# ME433_1.net
KiCad netlist of a schematic drawn in EAGLE
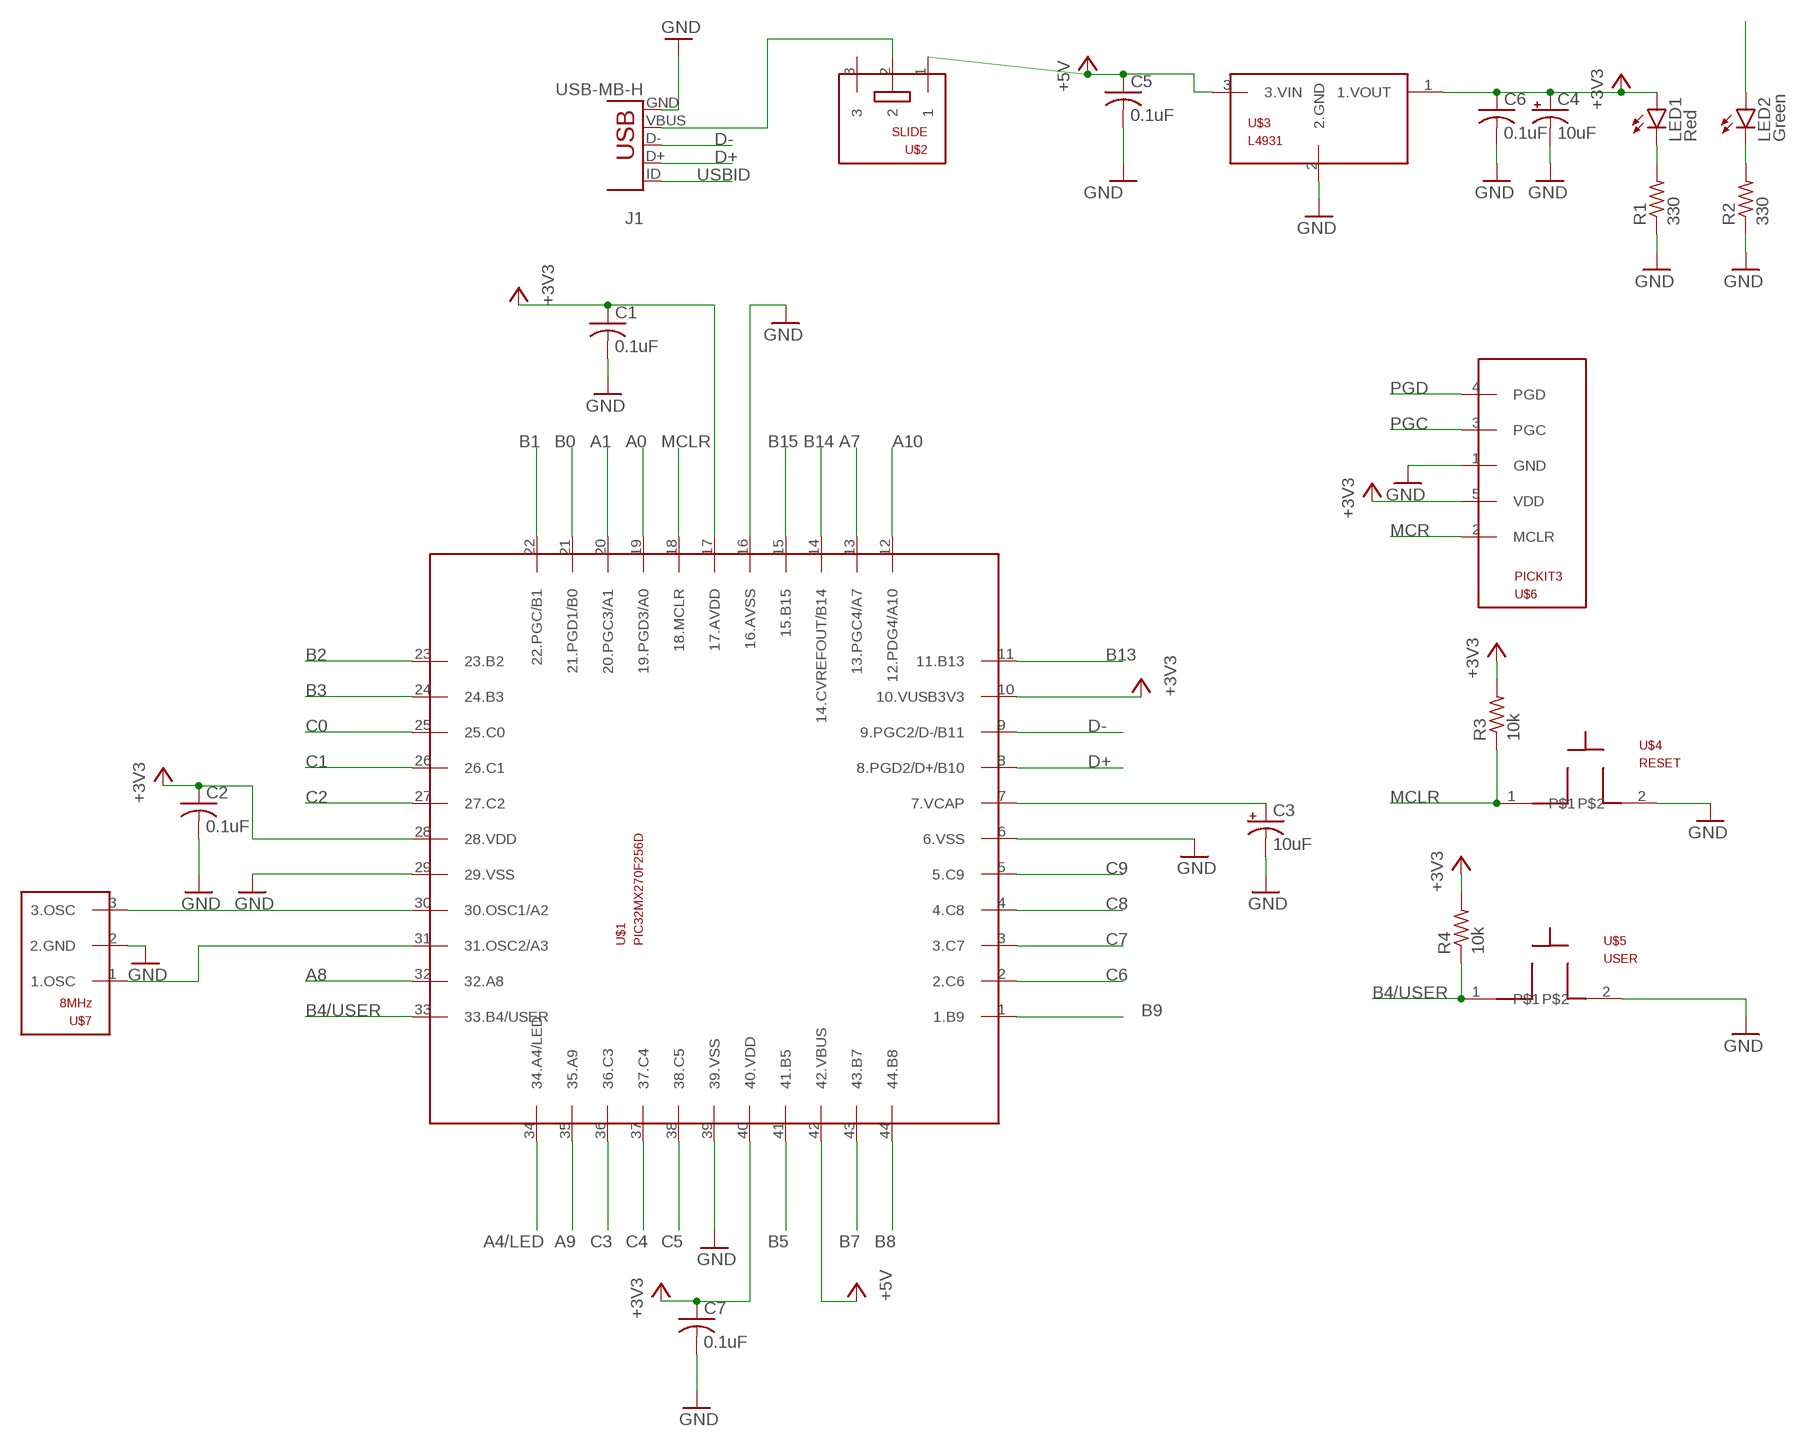
[diagram p0: schematic, sheet 1]

(export (version "E")
  (design (tool "Eeschema 10.0.6"))
  (components
    (comp (ref "C1")
      (value "0.1uF")
      (footprint "eagle-import:C025-025X050")
      (libsource (lib "eagle-import") (part "C-US025-025X050"))
    )
    (comp (ref "C2")
      (value "0.1uF")
      (footprint "eagle-import:C025-025X050")
      (libsource (lib "eagle-import") (part "C-US025-025X050"))
    )
    (comp (ref "C3")
      (value "10uF")
      (footprint "eagle-import:B45181B")
      (libsource (lib "eagle-import") (part "CPOL-USB45181B"))
    )
    (comp (ref "C4")
      (value "10uF")
      (footprint "eagle-import:B45181B")
      (libsource (lib "eagle-import") (part "CPOL-USB45181B"))
    )
    (comp (ref "C5")
      (value "0.1uF")
      (footprint "eagle-import:C025-025X050")
      (libsource (lib "eagle-import") (part "C-US025-025X050"))
    )
    (comp (ref "C6")
      (value "0.1uF")
      (footprint "eagle-import:C025-025X050")
      (libsource (lib "eagle-import") (part "C-US025-025X050"))
    )
    (comp (ref "C7")
      (value "0.1uF")
      (footprint "eagle-import:C025-025X050")
      (libsource (lib "eagle-import") (part "C-US025-025X050"))
    )
    (comp (ref "J1")
      (value "USB-MB-H")
      (footprint "eagle-import:USB-MB-H")
      (libsource (lib "eagle-import") (part "USB-MB-H"))
    )
    (comp (ref "LED1")
      (value "Red")
      (footprint "eagle-import:LED3MM")
      (libsource (lib "eagle-import") (part "LED3MM"))
    )
    (comp (ref "LED2")
      (value "Green")
      (footprint "eagle-import:LED3MM")
      (libsource (lib "eagle-import") (part "LED3MM"))
    )
    (comp (ref "R1")
      (value "330")
      (footprint "eagle-import:0207_10")
      (libsource (lib "eagle-import") (part "R-US_0207/10"))
    )
    (comp (ref "R2")
      (value "330")
      (footprint "eagle-import:0207_10")
      (libsource (lib "eagle-import") (part "R-US_0207/10"))
    )
    (comp (ref "R3")
      (value "10k")
      (footprint "eagle-import:0207_10")
      (libsource (lib "eagle-import") (part "R-US_0207/10"))
    )
    (comp (ref "R4")
      (value "10k")
      (footprint "eagle-import:0207_10")
      (libsource (lib "eagle-import") (part "R-US_0207/10"))
    )
    (comp (ref "U$1")
      (value "PIC32MX270F256D")
      (footprint "eagle-import:TQFP44")
      (libsource (lib "eagle-import") (part "PIC32MX270F256D"))
    )
    (comp (ref "U$2")
      (value "SLIDE")
      (footprint "eagle-import:SLIDE")
      (libsource (lib "eagle-import") (part "SLIDE"))
    )
    (comp (ref "U$3")
      (value "L4931")
      (footprint "eagle-import:1X03VREG")
      (libsource (lib "eagle-import") (part "L4931"))
    )
    (comp (ref "U$4")
      (value "RESET")
      (footprint "eagle-import:PB")
      (libsource (lib "eagle-import") (part "PB"))
    )
    (comp (ref "U$5")
      (value "USER")
      (footprint "eagle-import:PB")
      (libsource (lib "eagle-import") (part "PB"))
    )
    (comp (ref "U$6")
      (value "PICKIT3")
      (footprint "eagle-import:1X05")
      (libsource (lib "eagle-import") (part "PICKIT3"))
    )
    (comp (ref "U$7")
      (value "8MHz")
      (footprint "eagle-import:OSC")
      (libsource (lib "eagle-import") (part "OSC"))
    )
  )
  (nets
    (net (code "1") (name "+3V3") (class "Default")
      (node (ref "C1") (pin "1") (pinfunction "1_1") (pintype "passive"))
      (node (ref "C2") (pin "1") (pinfunction "1_1") (pintype "passive"))
      (node (ref "C4") (pin "+") (pinfunction "+_+") (pintype "passive"))
      (node (ref "C6") (pin "1") (pinfunction "1_1") (pintype "passive"))
      (node (ref "C7") (pin "1") (pinfunction "1_1") (pintype "passive"))
      (node (ref "LED1") (pin "A") (pinfunction "A_A") (pintype "passive"))
      (node (ref "R3") (pin "2") (pinfunction "2_2") (pintype "passive"))
      (node (ref "R4") (pin "2") (pinfunction "2_2") (pintype "passive"))
      (node (ref "U$1") (pin "10") (pinfunction "10.VUSB3V3_10") (pintype "bidirectional"))
      (node (ref "U$1") (pin "17") (pinfunction "17.AVDD_17") (pintype "bidirectional"))
      (node (ref "U$1") (pin "28") (pinfunction "28.VDD_28") (pintype "bidirectional"))
      (node (ref "U$1") (pin "40") (pinfunction "40.VDD_40") (pintype "bidirectional"))
      (node (ref "U$3") (pin "1") (pinfunction "1.VOUT_1") (pintype "bidirectional"))
      (node (ref "U$6") (pin "5") (pinfunction "VDD_5") (pintype "bidirectional"))
    )
    (net (code "2") (name "+5V") (class "Default")
      (node (ref "C5") (pin "1") (pinfunction "1_1") (pintype "passive"))
      (node (ref "U$1") (pin "42") (pinfunction "42.VBUS_42") (pintype "bidirectional"))
      (node (ref "U$2") (pin "1") (pinfunction "1_1") (pintype "bidirectional"))
      (node (ref "U$3") (pin "3") (pinfunction "3.VIN_3") (pintype "bidirectional"))
    )
    (net (code "3") (name "/A0") (class "Default")
      (node (ref "U$1") (pin "19") (pinfunction "19.PGD3/A0_19") (pintype "bidirectional"))
    )
    (net (code "4") (name "/A1") (class "Default")
      (node (ref "U$1") (pin "20") (pinfunction "20.PGC3/A1_20") (pintype "bidirectional"))
    )
    (net (code "5") (name "/A4{slash}LED") (class "Default")
      (node (ref "LED2") (pin "A") (pinfunction "A_A") (pintype "passive"))
      (node (ref "U$1") (pin "34") (pinfunction "34.A4/LED_34") (pintype "bidirectional"))
    )
    (net (code "6") (name "/A7") (class "Default")
      (node (ref "U$1") (pin "13") (pinfunction "13.PGC4/A7_13") (pintype "bidirectional"))
    )
    (net (code "7") (name "/A8") (class "Default")
      (node (ref "U$1") (pin "32") (pinfunction "32.A8_32") (pintype "bidirectional"))
    )
    (net (code "8") (name "/A9") (class "Default")
      (node (ref "U$1") (pin "35") (pinfunction "35.A9_35") (pintype "bidirectional"))
    )
    (net (code "9") (name "/A10") (class "Default")
      (node (ref "U$1") (pin "12") (pinfunction "12.PDG4/A10_12") (pintype "bidirectional"))
    )
    (net (code "10") (name "/B0") (class "Default")
      (node (ref "U$1") (pin "21") (pinfunction "21.PGD1/B0_21") (pintype "bidirectional"))
    )
    (net (code "11") (name "/B1") (class "Default")
      (node (ref "U$1") (pin "22") (pinfunction "22.PGC/B1_22") (pintype "bidirectional"))
    )
    (net (code "12") (name "/B2") (class "Default")
      (node (ref "U$1") (pin "23") (pinfunction "23.B2_23") (pintype "bidirectional"))
    )
    (net (code "13") (name "/B3") (class "Default")
      (node (ref "U$1") (pin "24") (pinfunction "24.B3_24") (pintype "bidirectional"))
    )
    (net (code "14") (name "/B4{slash}USER") (class "Default")
      (node (ref "R4") (pin "1") (pinfunction "1_1") (pintype "passive"))
      (node (ref "U$1") (pin "33") (pinfunction "33.B4/USER_33") (pintype "bidirectional"))
      (node (ref "U$5") (pin "1") (pinfunction "P$1_1") (pintype "bidirectional"))
    )
    (net (code "15") (name "/B5") (class "Default")
      (node (ref "U$1") (pin "41") (pinfunction "41.B5_41") (pintype "bidirectional"))
    )
    (net (code "16") (name "/B7") (class "Default")
      (node (ref "U$1") (pin "43") (pinfunction "43.B7_43") (pintype "bidirectional"))
    )
    (net (code "17") (name "/B8") (class "Default")
      (node (ref "U$1") (pin "44") (pinfunction "44.B8_44") (pintype "bidirectional"))
    )
    (net (code "18") (name "/B9") (class "Default")
      (node (ref "U$1") (pin "1") (pinfunction "1.B9_1") (pintype "bidirectional"))
    )
    (net (code "19") (name "/B13") (class "Default")
      (node (ref "U$1") (pin "11") (pinfunction "11.B13_11") (pintype "bidirectional"))
    )
    (net (code "20") (name "/B14") (class "Default")
      (node (ref "U$1") (pin "14") (pinfunction "14.CVREFOUT/B14_14") (pintype "bidirectional"))
    )
    (net (code "21") (name "/B15") (class "Default")
      (node (ref "U$1") (pin "15") (pinfunction "15.B15_15") (pintype "bidirectional"))
    )
    (net (code "22") (name "/C0") (class "Default")
      (node (ref "U$1") (pin "25") (pinfunction "25.C0_25") (pintype "bidirectional"))
    )
    (net (code "23") (name "/C1") (class "Default")
      (node (ref "U$1") (pin "26") (pinfunction "26.C1_26") (pintype "bidirectional"))
    )
    (net (code "24") (name "/C2") (class "Default")
      (node (ref "U$1") (pin "27") (pinfunction "27.C2_27") (pintype "bidirectional"))
    )
    (net (code "25") (name "/C3") (class "Default")
      (node (ref "U$1") (pin "36") (pinfunction "36.C3_36") (pintype "bidirectional"))
    )
    (net (code "26") (name "/C4") (class "Default")
      (node (ref "U$1") (pin "37") (pinfunction "37.C4_37") (pintype "bidirectional"))
    )
    (net (code "27") (name "/C5") (class "Default")
      (node (ref "U$1") (pin "38") (pinfunction "38.C5_38") (pintype "bidirectional"))
    )
    (net (code "28") (name "/C6") (class "Default")
      (node (ref "U$1") (pin "2") (pinfunction "2.C6_2") (pintype "bidirectional"))
    )
    (net (code "29") (name "/C7") (class "Default")
      (node (ref "U$1") (pin "3") (pinfunction "3.C7_3") (pintype "bidirectional"))
    )
    (net (code "30") (name "/C8") (class "Default")
      (node (ref "U$1") (pin "4") (pinfunction "4.C8_4") (pintype "bidirectional"))
    )
    (net (code "31") (name "/C9") (class "Default")
      (node (ref "U$1") (pin "5") (pinfunction "5.C9_5") (pintype "bidirectional"))
    )
    (net (code "32") (name "/D+") (class "Default")
      (node (ref "J1") (pin "D+") (pinfunction "D+_D+") (pintype "bidirectional"))
      (node (ref "U$1") (pin "8") (pinfunction "8.PGD2/D+/B10_8") (pintype "bidirectional"))
    )
    (net (code "33") (name "/D-") (class "Default")
      (node (ref "J1") (pin "D-") (pinfunction "D-_D-") (pintype "bidirectional"))
      (node (ref "U$1") (pin "9") (pinfunction "9.PGC2/D-/B11_9") (pintype "bidirectional"))
    )
    (net (code "34") (name "/MCLR") (class "Default")
      (node (ref "R3") (pin "1") (pinfunction "1_1") (pintype "passive"))
      (node (ref "U$1") (pin "18") (pinfunction "18.MCLR_18") (pintype "bidirectional"))
      (node (ref "U$4") (pin "1") (pinfunction "P$1_1") (pintype "bidirectional"))
    )
    (net (code "35") (name "/MCR") (class "Default")
      (node (ref "U$6") (pin "2") (pinfunction "MCLR_2") (pintype "bidirectional"))
    )
    (net (code "36") (name "/PGC") (class "Default")
      (node (ref "U$6") (pin "3") (pinfunction "PGC_3") (pintype "bidirectional"))
    )
    (net (code "37") (name "/PGD") (class "Default")
      (node (ref "U$6") (pin "4") (pinfunction "PGD_4") (pintype "bidirectional"))
    )
    (net (code "38") (name "/USBID") (class "Default")
      (node (ref "J1") (pin "ID") (pinfunction "ID_ID") (pintype "bidirectional"))
    )
    (net (code "39") (name "GND") (class "Default")
      (node (ref "C1") (pin "2") (pinfunction "2_2") (pintype "passive"))
      (node (ref "C2") (pin "2") (pinfunction "2_2") (pintype "passive"))
      (node (ref "C3") (pin "-") (pinfunction "-_-") (pintype "passive"))
      (node (ref "C4") (pin "-") (pinfunction "-_-") (pintype "passive"))
      (node (ref "C5") (pin "2") (pinfunction "2_2") (pintype "passive"))
      (node (ref "C6") (pin "2") (pinfunction "2_2") (pintype "passive"))
      (node (ref "C7") (pin "2") (pinfunction "2_2") (pintype "passive"))
      (node (ref "J1") (pin "GND") (pinfunction "GND_GND") (pintype "bidirectional"))
      (node (ref "R1") (pin "1") (pinfunction "1_1") (pintype "passive"))
      (node (ref "R2") (pin "1") (pinfunction "1_1") (pintype "passive"))
      (node (ref "U$1") (pin "16") (pinfunction "16.AVSS_16") (pintype "bidirectional"))
      (node (ref "U$1") (pin "29") (pinfunction "29.VSS_29") (pintype "bidirectional"))
      (node (ref "U$1") (pin "39") (pinfunction "39.VSS_39") (pintype "bidirectional"))
      (node (ref "U$1") (pin "6") (pinfunction "6.VSS_6") (pintype "bidirectional"))
      (node (ref "U$3") (pin "2") (pinfunction "2.GND_2") (pintype "bidirectional"))
      (node (ref "U$4") (pin "2") (pinfunction "P$2_2") (pintype "bidirectional"))
      (node (ref "U$5") (pin "2") (pinfunction "P$2_2") (pintype "bidirectional"))
      (node (ref "U$6") (pin "1") (pinfunction "GND_1") (pintype "bidirectional"))
      (node (ref "U$7") (pin "2") (pinfunction "2.GND_2") (pintype "bidirectional"))
    )
    (net (code "40") (name "Net-(J1-PadVBUS)") (class "Default")
      (node (ref "J1") (pin "VBUS") (pinfunction "VBUS_VBUS") (pintype "bidirectional"))
      (node (ref "U$2") (pin "2") (pinfunction "2_2") (pintype "bidirectional"))
    )
    (net (code "41") (name "Net-(LED1-C)") (class "Default")
      (node (ref "LED1") (pin "K") (pinfunction "C_K") (pintype "passive"))
      (node (ref "R1") (pin "2") (pinfunction "2_2") (pintype "passive"))
    )
    (net (code "42") (name "Net-(LED2-C)") (class "Default")
      (node (ref "LED2") (pin "K") (pinfunction "C_K") (pintype "passive"))
      (node (ref "R2") (pin "2") (pinfunction "2_2") (pintype "passive"))
    )
    (net (code "43") (name "Net-(U$1-7.VCAP)") (class "Default")
      (node (ref "C3") (pin "+") (pinfunction "+_+") (pintype "passive"))
      (node (ref "U$1") (pin "7") (pinfunction "7.VCAP_7") (pintype "bidirectional"))
    )
    (net (code "44") (name "Net-(U$1-30.OSC1{slash}A2)") (class "Default")
      (node (ref "U$1") (pin "30") (pinfunction "30.OSC1/A2_30") (pintype "bidirectional"))
      (node (ref "U$7") (pin "3") (pinfunction "3.OSC_3") (pintype "bidirectional"))
    )
    (net (code "45") (name "Net-(U$1-31.OSC2{slash}A3)") (class "Default")
      (node (ref "U$1") (pin "31") (pinfunction "31.OSC2/A3_31") (pintype "bidirectional"))
      (node (ref "U$7") (pin "1") (pinfunction "1.OSC_1") (pintype "bidirectional"))
    )
    (net (code "46") (name "unconnected-(U$2-Pad3)") (class "Default")
      (node (ref "U$2") (pin "3") (pinfunction "3_3") (pintype "bidirectional"))
    )
  )
)
